# SolarSprinkler.net
KiCad netlist of a schematic drawn in EAGLE
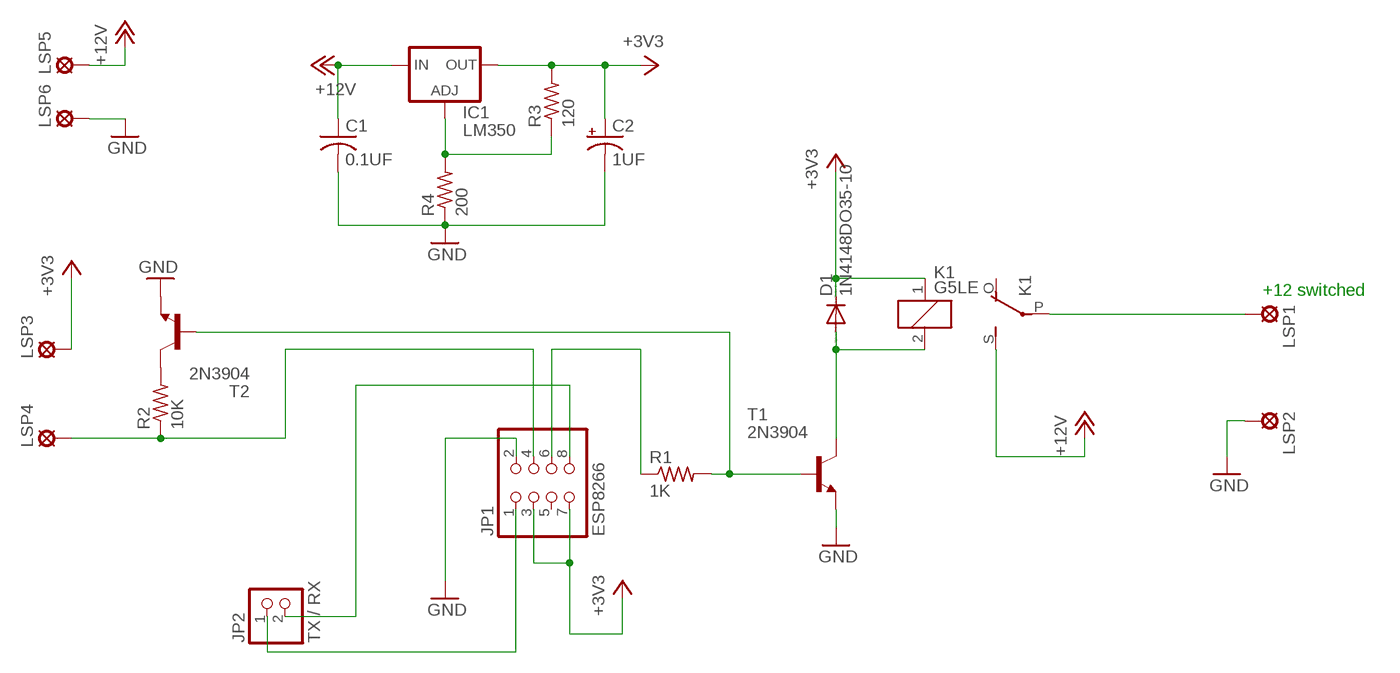
[diagram p0: schematic, sheet 1]

(export (version "E")
  (design (tool "Eeschema 10.0.6"))
  (components
    (comp (ref "C1")
      (value "0.1UF")
      (footprint "eagle-import:C025-030X050")
      (libsource (lib "eagle-import") (part "C-US025-030X050"))
    )
    (comp (ref "C2")
      (value "1UF")
      (footprint "eagle-import:E2,5-5")
      (libsource (lib "eagle-import") (part "CPOL-USE2.5-5"))
    )
    (comp (ref "D1")
      (value "1N4148DO35-10")
      (footprint "eagle-import:DO35-10")
      (libsource (lib "eagle-import") (part "1N4148DO35-10"))
    )
    (comp (ref "IC1")
      (value "LM350")
      (footprint "eagle-import:317TL")
      (libsource (lib "eagle-import") (part "LM317TL"))
    )
    (comp (ref "JP1")
      (value "ESP8266")
      (footprint "eagle-import:2X04")
      (libsource (lib "eagle-import") (part "PINHD-2X4"))
    )
    (comp (ref "JP2")
      (value "TX / RX")
      (footprint "eagle-import:1X02")
      (libsource (lib "eagle-import") (part "PINHD-1X2"))
    )
    (comp (ref "K1")
      (value "G5LE")
      (footprint "eagle-import:G5LE")
      (libsource (lib "eagle-import") (part "G5LE"))
    )
    (comp (ref "LSP1")
      (value "SE14")
      (footprint "eagle-import:SE14")
      (libsource (lib "eagle-import") (part "SE14"))
    )
    (comp (ref "LSP2")
      (value "SE14")
      (footprint "eagle-import:SE14")
      (libsource (lib "eagle-import") (part "SE14"))
    )
    (comp (ref "LSP3")
      (value "SE14")
      (footprint "eagle-import:SE14")
      (libsource (lib "eagle-import") (part "SE14"))
    )
    (comp (ref "LSP4")
      (value "SE14")
      (footprint "eagle-import:SE14")
      (libsource (lib "eagle-import") (part "SE14"))
    )
    (comp (ref "LSP5")
      (value "SE14")
      (footprint "eagle-import:SE14")
      (libsource (lib "eagle-import") (part "SE14"))
    )
    (comp (ref "LSP6")
      (value "SE14")
      (footprint "eagle-import:SE14")
      (libsource (lib "eagle-import") (part "SE14"))
    )
    (comp (ref "R1")
      (value "1K")
      (footprint "eagle-import:0309_12")
      (libsource (lib "eagle-import") (part "R-US_0309/12"))
    )
    (comp (ref "R2")
      (value "10K")
      (footprint "eagle-import:0309_12")
      (libsource (lib "eagle-import") (part "R-US_0309/12"))
    )
    (comp (ref "R3")
      (value "120")
      (footprint "eagle-import:0309_12")
      (libsource (lib "eagle-import") (part "R-US_0309/12"))
    )
    (comp (ref "R4")
      (value "200")
      (footprint "eagle-import:0309_12")
      (libsource (lib "eagle-import") (part "R-US_0309/12"))
    )
    (comp (ref "T1")
      (value "2N3904")
      (footprint "eagle-import:TO92")
      (libsource (lib "eagle-import") (part "2N3904"))
    )
    (comp (ref "T2")
      (value "2N3904")
      (footprint "eagle-import:TO92")
      (libsource (lib "eagle-import") (part "2N3904"))
    )
  )
  (nets
    (net (code "1") (name "+3V3") (class "Default")
      (node (ref "C2") (pin "+") (pinfunction "+_+") (pintype "passive"))
      (node (ref "D1") (pin "C") (pinfunction "C_C") (pintype "passive"))
      (node (ref "IC1") (pin "2") (pinfunction "OUT_2") (pintype "passive"))
      (node (ref "JP1") (pin "3") (pinfunction "3_3") (pintype "passive"))
      (node (ref "JP1") (pin "7") (pinfunction "7_7") (pintype "passive"))
      (node (ref "K1") (pin "1") (pinfunction "1_1") (pintype "passive"))
      (node (ref "LSP3") (pin "MP") (pinfunction "MP_MP") (pintype "passive"))
      (node (ref "R3") (pin "2") (pinfunction "2_2") (pintype "passive"))
    )
    (net (code "2") (name "+12V") (class "Default")
      (node (ref "C1") (pin "1") (pinfunction "1_1") (pintype "passive"))
      (node (ref "IC1") (pin "3") (pinfunction "IN_3") (pintype "input"))
      (node (ref "K1") (pin "S") (pinfunction "S_S") (pintype "passive"))
      (node (ref "LSP5") (pin "MP") (pinfunction "MP_MP") (pintype "passive"))
    )
    (net (code "3") (name "GND") (class "Default")
      (node (ref "C1") (pin "2") (pinfunction "2_2") (pintype "passive"))
      (node (ref "C2") (pin "-") (pinfunction "-_-") (pintype "passive"))
      (node (ref "JP1") (pin "2") (pinfunction "2_2") (pintype "passive"))
      (node (ref "LSP2") (pin "MP") (pinfunction "MP_MP") (pintype "passive"))
      (node (ref "LSP6") (pin "MP") (pinfunction "MP_MP") (pintype "passive"))
      (node (ref "R4") (pin "1") (pinfunction "1_1") (pintype "passive"))
      (node (ref "T1") (pin "3") (pinfunction "E_3") (pintype "passive"))
      (node (ref "T2") (pin "3") (pinfunction "E_3") (pintype "passive"))
    )
    (net (code "4") (name "Net-(IC1-ADJ)") (class "Default")
      (node (ref "IC1") (pin "1") (pinfunction "ADJ_1") (pintype "input"))
      (node (ref "R3") (pin "1") (pinfunction "1_1") (pintype "passive"))
      (node (ref "R4") (pin "2") (pinfunction "2_2") (pintype "passive"))
    )
    (net (code "5") (name "Net-(JP1-Pad1)") (class "Default")
      (node (ref "JP1") (pin "1") (pinfunction "1_1") (pintype "passive"))
      (node (ref "JP2") (pin "1") (pinfunction "1_1") (pintype "passive"))
    )
    (net (code "6") (name "Net-(JP1-Pad4)") (class "Default")
      (node (ref "JP1") (pin "4") (pinfunction "4_4") (pintype "passive"))
      (node (ref "LSP4") (pin "MP") (pinfunction "MP_MP") (pintype "passive"))
      (node (ref "R2") (pin "1") (pinfunction "1_1") (pintype "passive"))
    )
    (net (code "7") (name "Net-(JP1-Pad6)") (class "Default")
      (node (ref "JP1") (pin "6") (pinfunction "6_6") (pintype "passive"))
      (node (ref "R1") (pin "1") (pinfunction "1_1") (pintype "passive"))
    )
    (net (code "8") (name "Net-(JP1-Pad8)") (class "Default")
      (node (ref "JP1") (pin "8") (pinfunction "8_8") (pintype "passive"))
      (node (ref "JP2") (pin "2") (pinfunction "2_2") (pintype "passive"))
    )
    (net (code "9") (name "Net-(K1-PadP)") (class "Default")
      (node (ref "K1") (pin "P") (pinfunction "P_P") (pintype "passive"))
      (node (ref "LSP1") (pin "MP") (pinfunction "MP_MP") (pintype "passive"))
    )
    (net (code "10") (name "Net-(T1-B)") (class "Default")
      (node (ref "R1") (pin "2") (pinfunction "2_2") (pintype "passive"))
      (node (ref "T1") (pin "2") (pinfunction "B_2") (pintype "passive"))
      (node (ref "T2") (pin "2") (pinfunction "B_2") (pintype "passive"))
    )
    (net (code "11") (name "Net-(T1-C)") (class "Default")
      (node (ref "D1") (pin "A") (pinfunction "A_A") (pintype "passive"))
      (node (ref "K1") (pin "2") (pinfunction "2_2") (pintype "passive"))
      (node (ref "T1") (pin "1") (pinfunction "C_1") (pintype "passive"))
    )
    (net (code "12") (name "Net-(T2-C)") (class "Default")
      (node (ref "R2") (pin "2") (pinfunction "2_2") (pintype "passive"))
      (node (ref "T2") (pin "1") (pinfunction "C_1") (pintype "passive"))
    )
    (net (code "13") (name "unconnected-(JP1-Pad5)") (class "Default")
      (node (ref "JP1") (pin "5") (pinfunction "5_5") (pintype "passive"))
    )
    (net (code "14") (name "unconnected-(K1-PadO)") (class "Default")
      (node (ref "K1") (pin "O") (pinfunction "O_O") (pintype "passive"))
    )
  )
)
